# DualPhotodiode.net
KiCad netlist of a schematic drawn in EAGLE
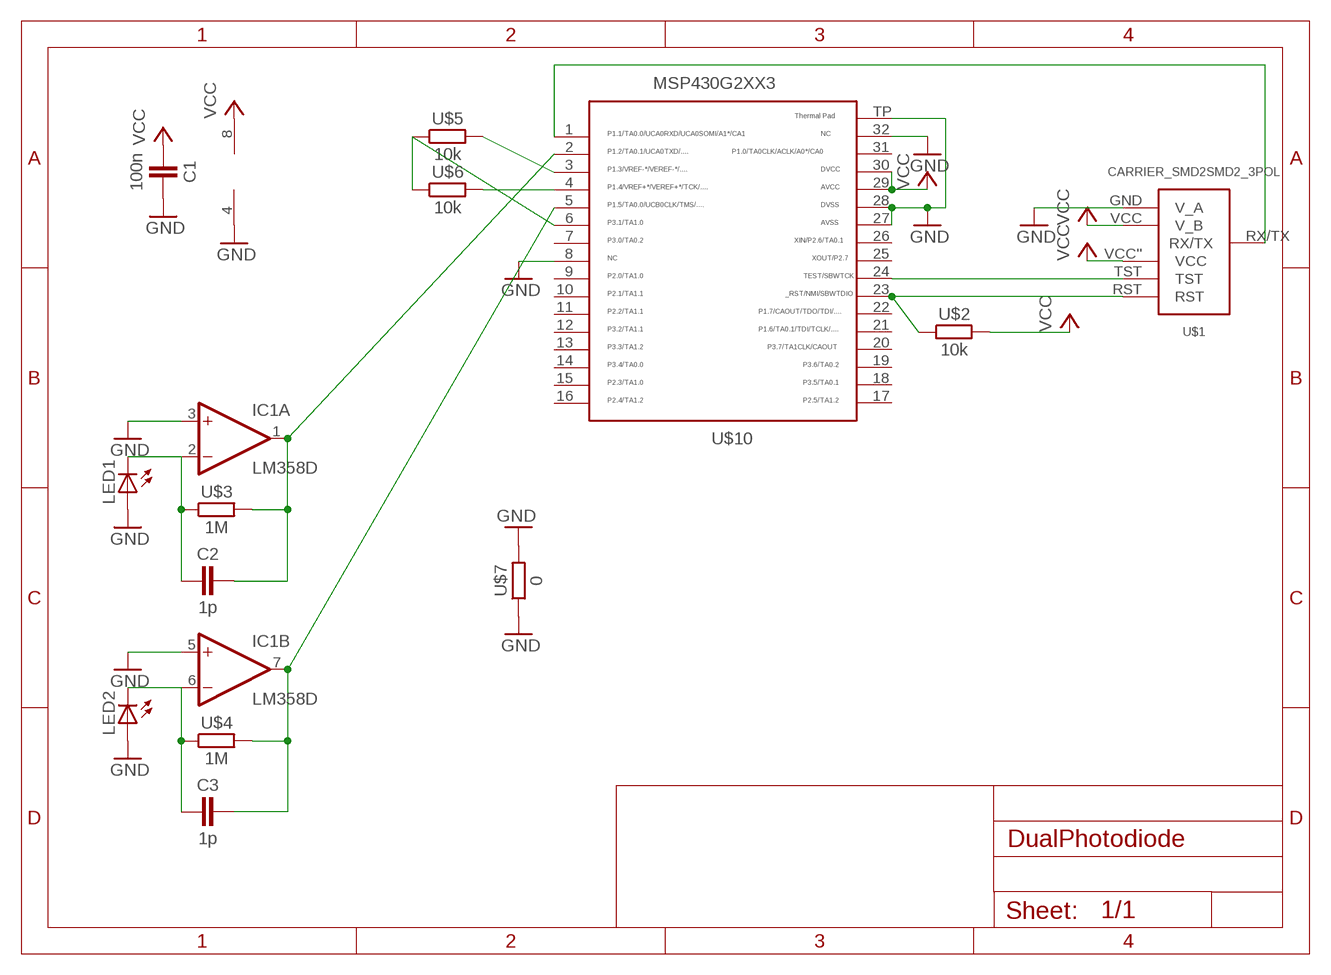
[diagram p0: schematic, sheet 1]

(export (version "E")
  (design (tool "Eeschema 10.0.6"))
  (components
    (comp (ref "C1")
      (value "100n")
      (footprint "eagle-import:603")
      (libsource (lib "eagle-import") (part "CAPACITOR"))
    )
    (comp (ref "C2")
      (value "1p")
      (footprint "eagle-import:603")
      (libsource (lib "eagle-import") (part "CAPACITOR"))
    )
    (comp (ref "C3")
      (value "1p")
      (footprint "eagle-import:603")
      (libsource (lib "eagle-import") (part "CAPACITOR"))
    )
    (comp (ref "IC1")
      (value "LM358D")
      (footprint "eagle-import:SO08")
      (libsource (lib "eagle-import") (part "LM358D"))
    )
    (comp (ref "LED1")
      (value "LEDCHIP-LED0805")
      (footprint "eagle-import:CHIP-LED0805")
      (libsource (lib "eagle-import") (part "LEDCHIP-LED0805"))
    )
    (comp (ref "LED2")
      (value "LEDCHIP-LED0805")
      (footprint "eagle-import:CHIP-LED0805")
      (libsource (lib "eagle-import") (part "LEDCHIP-LED0805"))
    )
    (comp (ref "U$1")
      (value "CARRIER_SMD2SMD2_3POL")
      (footprint "eagle-import:CARRIER_SMD2_3POL")
      (libsource (lib "eagle-import") (part "CARRIER_SMD2SMD2_3POL"))
    )
    (comp (ref "U$2")
      (value "10k")
      (footprint "eagle-import:603")
      (libsource (lib "eagle-import") (part "RESISTOR0603"))
    )
    (comp (ref "U$3")
      (value "1M")
      (footprint "eagle-import:603")
      (libsource (lib "eagle-import") (part "RESISTOR0603"))
    )
    (comp (ref "U$4")
      (value "1M")
      (footprint "eagle-import:603")
      (libsource (lib "eagle-import") (part "RESISTOR0603"))
    )
    (comp (ref "U$5")
      (value "10k")
      (footprint "eagle-import:603")
      (libsource (lib "eagle-import") (part "RESISTOR0603"))
    )
    (comp (ref "U$6")
      (value "10k")
      (footprint "eagle-import:603")
      (libsource (lib "eagle-import") (part "RESISTOR0603"))
    )
    (comp (ref "U$7")
      (value "0")
      (footprint "eagle-import:603")
      (libsource (lib "eagle-import") (part "RESISTOR0603"))
    )
    (comp (ref "U$10")
      (value "MSP430G2553")
      (footprint "eagle-import:QFN32")
      (libsource (lib "eagle-import") (part "MSP430G2553"))
    )
  )
  (nets
    (net (code "1") (name "GND") (class "Default")
      (node (ref "C1") (pin "2") (pinfunction "2_2") (pintype "passive"))
      (node (ref "IC1") (pin "3") (pinfunction "+IN_3") (pintype "input"))
      (node (ref "IC1") (pin "4") (pinfunction "V-_4") (pintype "power_in"))
      (node (ref "IC1") (pin "5") (pinfunction "+IN_5") (pintype "input"))
      (node (ref "LED1") (pin "A") (pinfunction "A_A") (pintype "passive"))
      (node (ref "LED2") (pin "A") (pinfunction "A_A") (pintype "passive"))
      (node (ref "U$1") (pin "GND") (pinfunction "V_A_GND") (pintype "bidirectional"))
      (node (ref "U$10") (pin "27") (pinfunction "27_27") (pintype "bidirectional"))
      (node (ref "U$10") (pin "28") (pinfunction "28_28") (pintype "bidirectional"))
      (node (ref "U$10") (pin "32") (pinfunction "32_32") (pintype "bidirectional"))
      (node (ref "U$10") (pin "8") (pinfunction "8_8") (pintype "bidirectional"))
      (node (ref "U$10") (pin "TP") (pinfunction "TP_TP") (pintype "bidirectional"))
      (node (ref "U$7") (pin "1") (pinfunction "1_1") (pintype "passive"))
      (node (ref "U$7") (pin "2") (pinfunction "2_2") (pintype "passive"))
    )
    (net (code "2") (name "Net-(IC1A--IN)") (class "Default")
      (node (ref "C2") (pin "1") (pinfunction "1_1") (pintype "passive"))
      (node (ref "IC1") (pin "2") (pinfunction "-IN_2") (pintype "input"))
      (node (ref "LED1") (pin "C") (pinfunction "C_C") (pintype "passive"))
      (node (ref "U$3") (pin "1") (pinfunction "1_1") (pintype "passive"))
    )
    (net (code "3") (name "Net-(IC1A-OUT)") (class "Default")
      (node (ref "C2") (pin "2") (pinfunction "2_2") (pintype "passive"))
      (node (ref "IC1") (pin "1") (pinfunction "OUT_1") (pintype "output"))
      (node (ref "U$10") (pin "2") (pinfunction "2_2") (pintype "bidirectional"))
      (node (ref "U$3") (pin "2") (pinfunction "2_2") (pintype "passive"))
    )
    (net (code "4") (name "Net-(IC1B--IN)") (class "Default")
      (node (ref "C3") (pin "1") (pinfunction "1_1") (pintype "passive"))
      (node (ref "IC1") (pin "6") (pinfunction "-IN_6") (pintype "input"))
      (node (ref "LED2") (pin "C") (pinfunction "C_C") (pintype "passive"))
      (node (ref "U$4") (pin "1") (pinfunction "1_1") (pintype "passive"))
    )
    (net (code "5") (name "Net-(IC1B-OUT)") (class "Default")
      (node (ref "C3") (pin "2") (pinfunction "2_2") (pintype "passive"))
      (node (ref "IC1") (pin "7") (pinfunction "OUT_7") (pintype "output"))
      (node (ref "U$10") (pin "5") (pinfunction "5_5") (pintype "bidirectional"))
      (node (ref "U$4") (pin "2") (pinfunction "2_2") (pintype "passive"))
    )
    (net (code "6") (name "Net-(U$1-PadRST)") (class "Default")
      (node (ref "U$1") (pin "RST") (pinfunction "RST_RST") (pintype "bidirectional"))
      (node (ref "U$10") (pin "23") (pinfunction "23_23") (pintype "bidirectional"))
      (node (ref "U$2") (pin "1") (pinfunction "1_1") (pintype "passive"))
    )
    (net (code "7") (name "Net-(U$1-PadRX{slash}TX)") (class "Default")
      (node (ref "U$1") (pin "RX/TX") (pinfunction "RX/TX_RX/TX") (pintype "bidirectional"))
      (node (ref "U$10") (pin "1") (pinfunction "1_1") (pintype "bidirectional"))
    )
    (net (code "8") (name "Net-(U$1-PadTST)") (class "Default")
      (node (ref "U$1") (pin "TST") (pinfunction "TST_TST") (pintype "bidirectional"))
      (node (ref "U$10") (pin "24") (pinfunction "24_24") (pintype "bidirectional"))
    )
    (net (code "9") (name "Net-(U$10-Pad3)") (class "Default")
      (node (ref "U$10") (pin "3") (pinfunction "3_3") (pintype "bidirectional"))
      (node (ref "U$5") (pin "2") (pinfunction "2_2") (pintype "passive"))
    )
    (net (code "10") (name "Net-(U$10-Pad4)") (class "Default")
      (node (ref "U$10") (pin "4") (pinfunction "4_4") (pintype "bidirectional"))
      (node (ref "U$6") (pin "2") (pinfunction "2_2") (pintype "passive"))
    )
    (net (code "11") (name "Net-(U$10-Pad6)") (class "Default")
      (node (ref "U$10") (pin "6") (pinfunction "6_6") (pintype "bidirectional"))
      (node (ref "U$5") (pin "1") (pinfunction "1_1") (pintype "passive"))
      (node (ref "U$6") (pin "1") (pinfunction "1_1") (pintype "passive"))
    )
    (net (code "12") (name "VCC") (class "Default")
      (node (ref "C1") (pin "1") (pinfunction "1_1") (pintype "passive"))
      (node (ref "IC1") (pin "8") (pinfunction "V+_8") (pintype "power_in"))
      (node (ref "U$1") (pin "VCC") (pinfunction "V_B_VCC") (pintype "bidirectional"))
      (node (ref "U$1") (pin "VCC''") (pinfunction "VCC_VCC''") (pintype "bidirectional"))
      (node (ref "U$10") (pin "29") (pinfunction "29_29") (pintype "bidirectional"))
      (node (ref "U$10") (pin "30") (pinfunction "30_30") (pintype "bidirectional"))
      (node (ref "U$2") (pin "2") (pinfunction "2_2") (pintype "passive"))
    )
    (net (code "13") (name "unconnected-(U$10-Pad7)") (class "Default")
      (node (ref "U$10") (pin "7") (pinfunction "7_7") (pintype "bidirectional"))
    )
    (net (code "14") (name "unconnected-(U$10-Pad9)") (class "Default")
      (node (ref "U$10") (pin "9") (pinfunction "9_9") (pintype "bidirectional"))
    )
    (net (code "15") (name "unconnected-(U$10-Pad10)") (class "Default")
      (node (ref "U$10") (pin "10") (pinfunction "10_10") (pintype "bidirectional"))
    )
    (net (code "16") (name "unconnected-(U$10-Pad11)") (class "Default")
      (node (ref "U$10") (pin "11") (pinfunction "11_11") (pintype "bidirectional"))
    )
    (net (code "17") (name "unconnected-(U$10-Pad12)") (class "Default")
      (node (ref "U$10") (pin "12") (pinfunction "12_12") (pintype "bidirectional"))
    )
    (net (code "18") (name "unconnected-(U$10-Pad13)") (class "Default")
      (node (ref "U$10") (pin "13") (pinfunction "13_13") (pintype "bidirectional"))
    )
    (net (code "19") (name "unconnected-(U$10-Pad14)") (class "Default")
      (node (ref "U$10") (pin "14") (pinfunction "14_14") (pintype "bidirectional"))
    )
    (net (code "20") (name "unconnected-(U$10-Pad15)") (class "Default")
      (node (ref "U$10") (pin "15") (pinfunction "15_15") (pintype "bidirectional"))
    )
    (net (code "21") (name "unconnected-(U$10-Pad16)") (class "Default")
      (node (ref "U$10") (pin "16") (pinfunction "16_16") (pintype "bidirectional"))
    )
    (net (code "22") (name "unconnected-(U$10-Pad17)") (class "Default")
      (node (ref "U$10") (pin "17") (pinfunction "17_17") (pintype "bidirectional"))
    )
    (net (code "23") (name "unconnected-(U$10-Pad18)") (class "Default")
      (node (ref "U$10") (pin "18") (pinfunction "18_18") (pintype "bidirectional"))
    )
    (net (code "24") (name "unconnected-(U$10-Pad19)") (class "Default")
      (node (ref "U$10") (pin "19") (pinfunction "19_19") (pintype "bidirectional"))
    )
    (net (code "25") (name "unconnected-(U$10-Pad20)") (class "Default")
      (node (ref "U$10") (pin "20") (pinfunction "20_20") (pintype "bidirectional"))
    )
    (net (code "26") (name "unconnected-(U$10-Pad21)") (class "Default")
      (node (ref "U$10") (pin "21") (pinfunction "21_21") (pintype "bidirectional"))
    )
    (net (code "27") (name "unconnected-(U$10-Pad22)") (class "Default")
      (node (ref "U$10") (pin "22") (pinfunction "22_22") (pintype "bidirectional"))
    )
    (net (code "28") (name "unconnected-(U$10-Pad25)") (class "Default")
      (node (ref "U$10") (pin "25") (pinfunction "25_25") (pintype "bidirectional"))
    )
    (net (code "29") (name "unconnected-(U$10-Pad26)") (class "Default")
      (node (ref "U$10") (pin "26") (pinfunction "26_26") (pintype "bidirectional"))
    )
    (net (code "30") (name "unconnected-(U$10-Pad31)") (class "Default")
      (node (ref "U$10") (pin "31") (pinfunction "31_31") (pintype "bidirectional"))
    )
  )
)
